# Differential_driver.net
KiCad netlist of a schematic drawn in Altium Designer
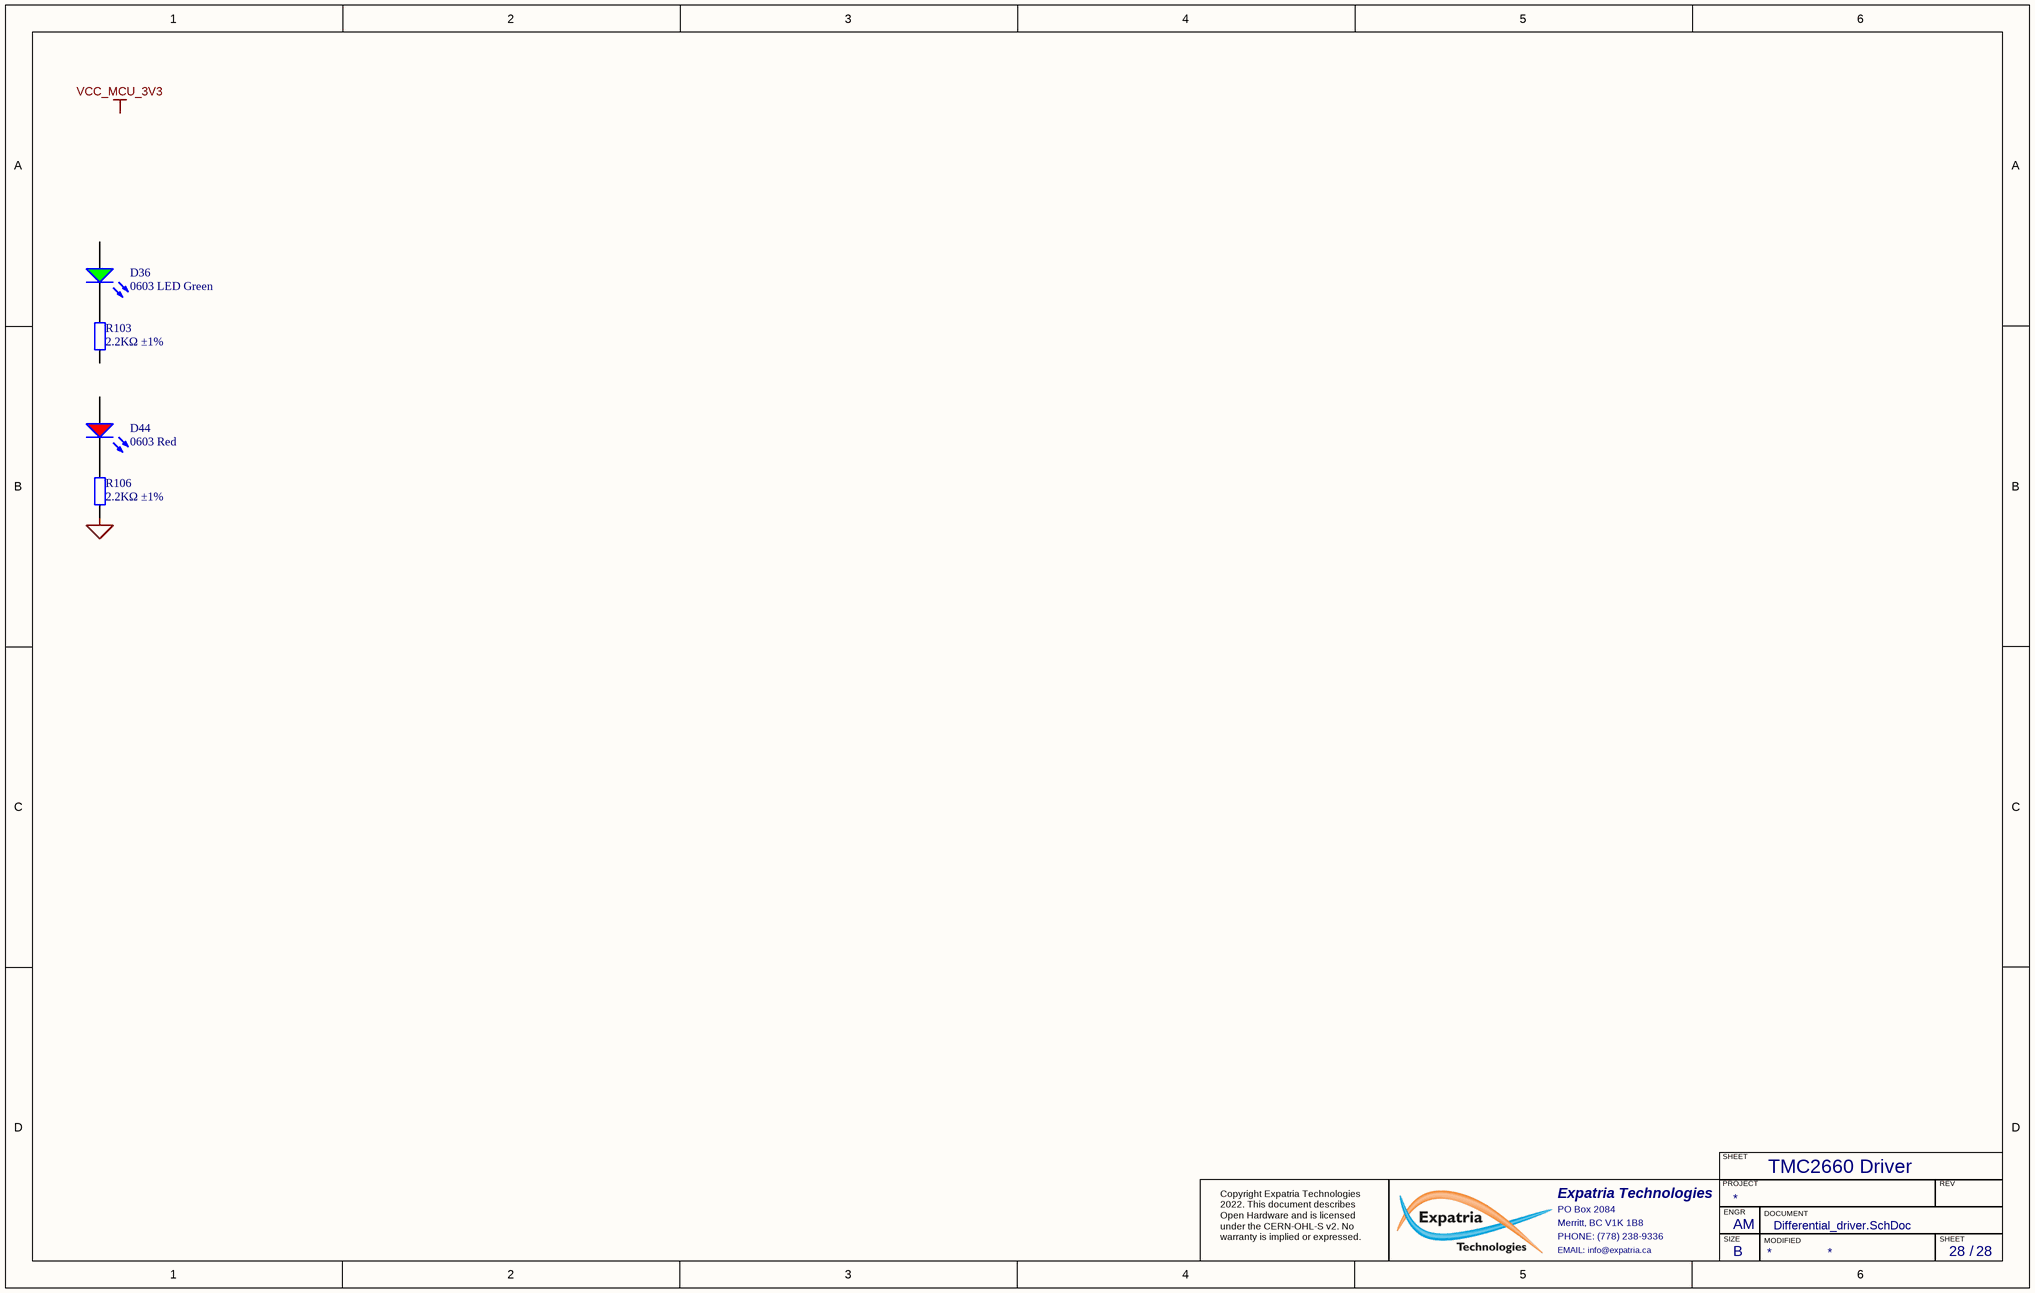
[diagram p0: Differential_driver.SchDoc]

(export (version "E")
  (design (tool "Eeschema 10.0.6"))
  (components
    (comp (ref "D36")
      (value "0603 LED Green")
      (footprint "0603_LED_S1 - GREEN")
      (fields
        (field (name "MANUFACTURER PART NUMBER") "19-217/GHC-YR1S2/3T")
        (field (name "MANUFACTURER") "Everlight Elec")
      )
      (libsource (lib "Sienci_Labs") (part "19-217/GHC-YR1S2/3T"))
    )
    (comp (ref "D44")
      (value "0603 Red")
      (footprint "0603_LED_S1")
      (fields
        (field (name "MANUFACTURER") "Everlight Elec")
        (field (name "MANUFACTURER PART NUMBER") "19-213SURC/S530-A3/TR8")
      )
      (libsource (lib "Sienci_Labs") (part "19-213SURC/S530-A3/TR8"))
    )
    (comp (ref "R103")
      (value "2.2KΩ ±1%")
      (footprint "0402_R")
      (description "Chip resistor")
      (fields
        (field (name "MANUFACTURER") "Uniroyal Elec")
        (field (name "MANUFACTURER PART NUMBER") "0402WGF2201TCE")
      )
      (libsource (lib "RES") (part "0402 2.2K (2201) 1%"))
    )
    (comp (ref "R106")
      (value "2.2KΩ ±1%")
      (footprint "0402_R")
      (description "Chip resistor")
      (fields
        (field (name "MANUFACTURER") "Uniroyal Elec")
        (field (name "MANUFACTURER PART NUMBER") "0402WGF2201TCE")
      )
      (libsource (lib "RES") (part "0402 2.2K (2201) 1%"))
    )
  )
  (nets
    (net (code "1") (name "MCU_GND") (class "Default")
      (node (ref "R106") (pin "1") (pinfunction "1_1") (pintype "passive"))
    )
    (net (code "2") (name "Net-(D36-PadK)") (class "Default")
      (node (ref "D36") (pin "K") (pinfunction "K_K") (pintype "passive"))
      (node (ref "R103") (pin "2") (pinfunction "2_2") (pintype "passive"))
    )
    (net (code "3") (name "Net-(D44-PadK)") (class "Default")
      (node (ref "D44") (pin "K") (pinfunction "K_K") (pintype "passive"))
      (node (ref "R106") (pin "2") (pinfunction "2_2") (pintype "passive"))
    )
    (net (code "5") (name "unconnected-(D36-PadA)") (class "Default")
      (node (ref "D36") (pin "A") (pinfunction "A_A") (pintype "passive"))
    )
    (net (code "6") (name "unconnected-(D44-PadA)") (class "Default")
      (node (ref "D44") (pin "A") (pinfunction "A_A") (pintype "passive"))
    )
    (net (code "7") (name "unconnected-(R103-Pad1)") (class "Default")
      (node (ref "R103") (pin "1") (pinfunction "1_1") (pintype "passive"))
    )
  )
)
